# SOIC8.net
KiCad netlist of a schematic drawn in EAGLE
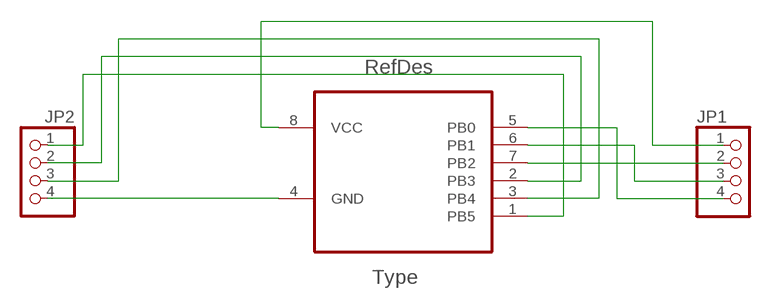
[diagram p0: schematic, sheet 1]

(export (version "E")
  (design (tool "Eeschema 10.0.6"))
  (components
    (comp (ref "JP1")
      (value "PINHD-1X4")
      (footprint "eagle-import:1X04")
      (libsource (lib "eagle-import") (part "PINHD-1X4"))
    )
    (comp (ref "JP2")
      (value "PINHD-1X4")
      (footprint "eagle-import:1X04")
      (libsource (lib "eagle-import") (part "PINHD-1X4"))
    )
    (comp (ref "U1")
      (value "ATTINY13-20SU")
      (footprint "eagle-import:SOIC127P798X216-8N")
      (libsource (lib "eagle-import") (part "ATTINY13-20SU"))
    )
  )
  (nets
    (net (code "1") (name "Net-(U1-GND)") (class "Default")
      (node (ref "JP2") (pin "4") (pinfunction "4_4") (pintype "passive"))
      (node (ref "U1") (pin "4") (pinfunction "GND_4") (pintype "passive"))
    )
    (net (code "2") (name "Net-(U1-PB0)") (class "Default")
      (node (ref "JP1") (pin "4") (pinfunction "4_4") (pintype "passive"))
      (node (ref "U1") (pin "5") (pinfunction "PB0_5") (pintype "bidirectional"))
    )
    (net (code "3") (name "Net-(U1-PB1)") (class "Default")
      (node (ref "JP1") (pin "3") (pinfunction "3_3") (pintype "passive"))
      (node (ref "U1") (pin "6") (pinfunction "PB1_6") (pintype "bidirectional"))
    )
    (net (code "4") (name "Net-(U1-PB2)") (class "Default")
      (node (ref "JP1") (pin "2") (pinfunction "2_2") (pintype "passive"))
      (node (ref "U1") (pin "7") (pinfunction "PB2_7") (pintype "bidirectional"))
    )
    (net (code "5") (name "Net-(U1-PB3)") (class "Default")
      (node (ref "JP2") (pin "2") (pinfunction "2_2") (pintype "passive"))
      (node (ref "U1") (pin "2") (pinfunction "PB3_2") (pintype "bidirectional"))
    )
    (net (code "6") (name "Net-(U1-PB4)") (class "Default")
      (node (ref "JP2") (pin "3") (pinfunction "3_3") (pintype "passive"))
      (node (ref "U1") (pin "3") (pinfunction "PB4_3") (pintype "bidirectional"))
    )
    (net (code "7") (name "Net-(U1-PB5)") (class "Default")
      (node (ref "JP2") (pin "1") (pinfunction "1_1") (pintype "passive"))
      (node (ref "U1") (pin "1") (pinfunction "PB5_1") (pintype "bidirectional"))
    )
    (net (code "8") (name "Net-(U1-VCC)") (class "Default")
      (node (ref "JP1") (pin "1") (pinfunction "1_1") (pintype "passive"))
      (node (ref "U1") (pin "8") (pinfunction "VCC_8") (pintype "power_in"))
    )
  )
)
